# HLW8012-Demo.net
KiCad netlist of a schematic drawn in Altium Designer
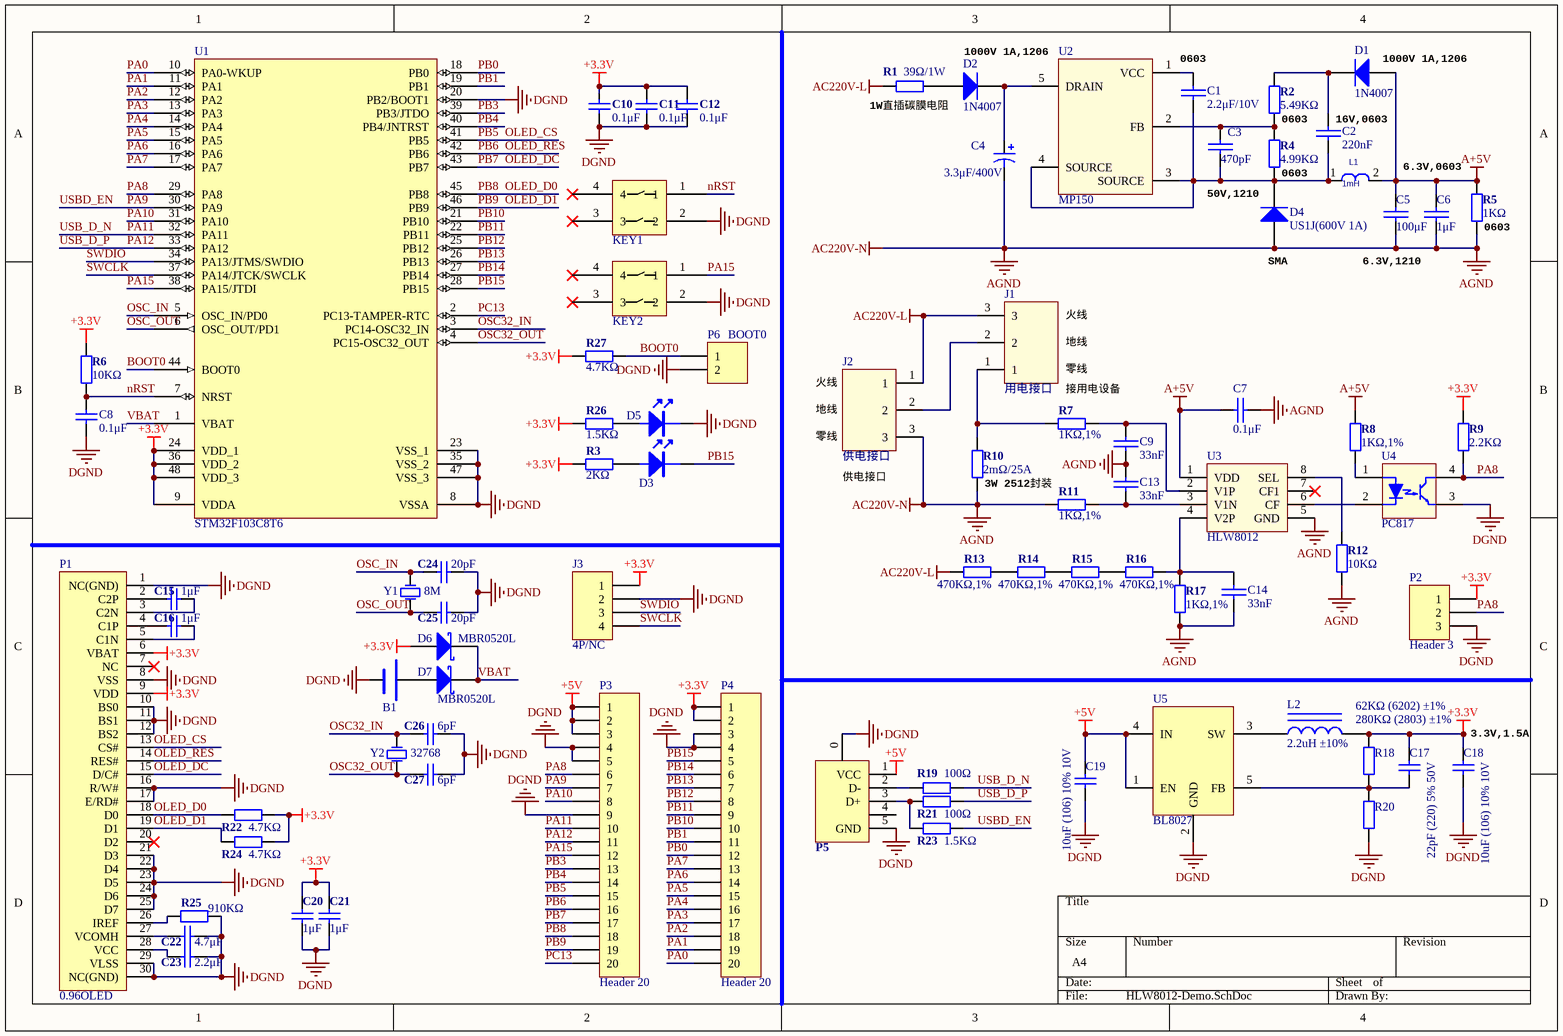
[diagram p0: HLW8012-Demo.SchDoc]

(export (version "E")
  (design (tool "Eeschema 10.0.6"))
  (components
    (comp (ref "B1")
      (value "BAT")
      (footprint "BATTERY SOCKET")
      (description "电池")
      (libsource (lib "OLED-0.96-Demo-MCU+Board") (part "BAT"))
    )
    (comp (ref "C1")
      (value "2.2μF/10V")
      (footprint "LC-0603_C")
      (description "贴片电容")
      (libsource (lib "原理图库") (part "CAP"))
    )
    (comp (ref "C2")
      (value "220nF")
      (footprint "LC-0603_C")
      (description "贴片电容")
      (libsource (lib "原理图库") (part "CAP"))
    )
    (comp (ref "C3")
      (value "470pF")
      (footprint "LC-0603_C")
      (description "贴片电容")
      (libsource (lib "原理图库") (part "CAP"))
    )
    (comp (ref "C4")
      (value "3.3μF/400V")
      (footprint "CAP-ELECT-TH-6.3X7")
      (description "直插电解电容")
      (fields (field (name "PUBLISHER") "Altium Limited"))
      (libsource (lib "Miscellaneous Devices") (part "Cap Pol1"))
    )
    (comp (ref "C5")
      (value "100μF")
      (footprint "LC-1210_C")
      (description "贴片电容")
      (libsource (lib "原理图库") (part "CAP"))
    )
    (comp (ref "C6")
      (value "1μF")
      (footprint "LC-0603_C")
      (description "贴片电容")
      (libsource (lib "原理图库") (part "CAP"))
    )
    (comp (ref "C7")
      (value "0.1μF")
      (footprint "LC-0603_C")
      (description "贴片电容")
      (libsource (lib "原理图库") (part "CAP"))
    )
    (comp (ref "C8")
      (value "0.1μF")
      (footprint "LC-0603_C")
      (description "贴片电容")
      (libsource (lib "FourAxis") (part "Cap"))
    )
    (comp (ref "C9")
      (value "33nF")
      (footprint "LC-0805_C")
      (description "贴片电容")
      (libsource (lib "原理图库") (part "CAP"))
    )
    (comp (ref "C10")
      (value "0.1μF")
      (footprint "LC-0603_C")
      (description "贴片电容")
      (libsource (lib "FourAxis") (part "Cap"))
    )
    (comp (ref "C11")
      (value "0.1μF")
      (footprint "LC-0603_C")
      (description "贴片电容")
      (libsource (lib "FourAxis") (part "Cap"))
    )
    (comp (ref "C12")
      (value "0.1μF")
      (footprint "LC-0603_C")
      (description "贴片电容")
      (libsource (lib "FourAxis") (part "Cap"))
    )
    (comp (ref "C13")
      (value "33nF")
      (footprint "LC-0805_C")
      (description "贴片电容")
      (libsource (lib "原理图库") (part "CAP"))
    )
    (comp (ref "C14")
      (value "33nF")
      (footprint "LC-0805_C")
      (description "贴片电容")
      (libsource (lib "原理图库") (part "CAP"))
    )
    (comp (ref "C15")
      (value "1μF")
      (footprint "LC-0603_C")
      (description "贴片电容")
      (libsource (lib "FourAxis") (part "Cap"))
    )
    (comp (ref "C16")
      (value "1μF")
      (footprint "LC-0603_C")
      (description "贴片电容")
      (libsource (lib "FourAxis") (part "Cap"))
    )
    (comp (ref "C17")
      (value "22pF (220) 5% 50V")
      (footprint "LC-0603_C")
      (description "贴片电容")
      (libsource (lib "Miscellaneous Devices LC") (part "0402 22pF (220) 5% 50V"))
    )
    (comp (ref "C18")
      (value "10uF (106) 10% 10V")
      (footprint "LC-0603_C")
      (description "贴片电容")
      (libsource (lib "Miscellaneous Devices LC") (part "0603 10uF (106) 10% 10V"))
    )
    (comp (ref "C19")
      (value "10uF (106) 10% 10V")
      (footprint "LC-0603_C")
      (description "贴片电容")
      (libsource (lib "Miscellaneous Devices LC") (part "0603 10uF (106) 10% 10V"))
    )
    (comp (ref "C20")
      (value "1μF")
      (footprint "LC-0603_C")
      (description "贴片电容")
      (libsource (lib "FourAxis") (part "Cap"))
    )
    (comp (ref "C21")
      (value "1μF")
      (footprint "LC-0603_C")
      (description "贴片电容")
      (libsource (lib "FourAxis") (part "Cap"))
    )
    (comp (ref "C22")
      (value "4.7μF")
      (footprint "LC-0603_C")
      (description "贴片电容")
      (libsource (lib "FourAxis") (part "Cap"))
    )
    (comp (ref "C23")
      (value "2.2μF")
      (footprint "LC-0603_C")
      (description "贴片电容")
      (libsource (lib "FourAxis") (part "Cap"))
    )
    (comp (ref "C24")
      (value "20pF")
      (footprint "LC-0603_C")
      (description "贴片电容")
      (libsource (lib "FourAxis") (part "Cap"))
    )
    (comp (ref "C25")
      (value "20pF")
      (footprint "LC-0603_C")
      (description "贴片电容")
      (libsource (lib "FourAxis") (part "Cap"))
    )
    (comp (ref "C26")
      (value "6pF")
      (footprint "LC-0603_C")
      (description "贴片电容")
      (libsource (lib "FourAxis") (part "Cap"))
    )
    (comp (ref "C27")
      (value "6pF")
      (footprint "LC-0603_C")
      (description "贴片电容")
      (libsource (lib "FourAxis") (part "Cap"))
    )
    (comp (ref "D1")
      (value "1N4007")
      (footprint "LC-SMA(DO-214AC)_S1")
      (description "贴片二极管")
      (fields (field (name "PUBLISHER") "Altium Limited"))
      (libsource (lib "Miscellaneous Devices") (part "Diode 1N5408"))
    )
    (comp (ref "D2")
      (value "1N4007")
      (footprint "LC-SMA(DO-214AC)_S1")
      (description "贴片二极管")
      (fields (field (name "PUBLISHER") "Altium Limited"))
      (libsource (lib "Miscellaneous Devices") (part "Diode 1N5408"))
    )
    (comp (ref "D3")
      (value "POWER")
      (footprint "LC-0603_LED_S1")
      (description "发光二极管")
      (libsource (lib "原理图库") (part "LED1"))
    )
    (comp (ref "D4")
      (value "US1J(600V 1A)")
      (footprint "LC-SMA(DO-214AC)_S1")
      (description "贴片二极管")
      (fields (field (name "PUBLISHER") "Altium Limited"))
      (libsource (lib "Miscellaneous Devices") (part "Diode 1N5408"))
    )
    (comp (ref "D5")
      (value "POWER")
      (footprint "LC-0603_LED_S1")
      (description "发光二极管")
      (libsource (lib "OLED-0.96-Demo-MCU+Board") (part "LED1"))
    )
    (comp (ref "D6")
      (value "MBR0520L")
      (footprint "LC-SOD-123")
      (description "贴片肖特基二极管")
      (fields (field (name "PUBLISHER") "Altium Limited"))
      (libsource (lib "USB-UART-RJ45") (part "Diode 18TQ045"))
    )
    (comp (ref "D7")
      (value "MBR0520L")
      (footprint "LC-SOD-123")
      (description "贴片肖特基二极管")
      (fields (field (name "PUBLISHER") "Altium Limited"))
      (libsource (lib "USB-UART-RJ45") (part "Diode 18TQ045"))
    )
    (comp (ref "J1")
      (value "用电接口")
      (footprint "3.81-3P")
      (description "直插接线端子")
      (libsource (lib "") (part "Port-3P_1"))
    )
    (comp (ref "J2")
      (value "供电接口")
      (footprint "3.81-3P")
      (description "直插接线端子")
      (libsource (lib "HLW8012-Demo") (part "Port-3P"))
    )
    (comp (ref "J3")
      (value "4P/NC")
      (footprint "HDR1X4")
      (description "接口")
      (fields (field (name "PUBLISHER") "Altium Limited"))
      (libsource (lib "Miscellaneous Connectors") (part "Header 4"))
    )
    (comp (ref "KEY1")
      (value "KEY")
      (footprint "KEY_4X4 - 6*6")
      (description "贴片轻触开关")
      (libsource (lib "STM32") (part "KEY"))
    )
    (comp (ref "KEY2")
      (value "KEY")
      (footprint "KEY_4X4 - 6*6")
      (description "贴片轻触开关")
      (libsource (lib "STM32") (part "KEY"))
    )
    (comp (ref "L1") (value "1mH") (description "直插绕线电感") (libsource (lib "*") (part "IND_8")))
    (comp (ref "L2")
      (value "2.2uH ±10%")
      (footprint "LC-0805_L")
      (description "贴片电感")
      (libsource (lib "Miscellaneous Devices LC") (part "0805 2.2uH 10%"))
    )
    (comp (ref "P1")
      (value "0.96OLED")
      (footprint "OLED_0.96")
      (description "接口")
      (fields (field (name "PUBLISHER") "Altium Limited"))
      (libsource (lib "HLW8012-Demo") (part "0.96OLED"))
    )
    (comp (ref "P2")
      (value "Header 3")
      (footprint "HDR1X3")
      (description "Header, 3-Pin")
      (fields (field (name "PUBLISHER") "Altium Limited"))
      (libsource (lib "Miscellaneous Connectors") (part "Header 3"))
    )
    (comp (ref "P3")
      (value "Header 20")
      (footprint "HDR1X20")
      (description "Header, 20-Pin")
      (fields (field (name "PUBLISHER") "Altium Limited"))
      (libsource (lib "Miscellaneous Connectors") (part "Header 20"))
    )
    (comp (ref "P4")
      (value "Header 20")
      (footprint "HDR1X20")
      (description "Header, 20-Pin")
      (fields (field (name "PUBLISHER") "Altium Limited"))
      (libsource (lib "Miscellaneous Connectors") (part "Header 20"))
    )
    (comp (ref "P5")
      (value "Micro USB,母头")
      (footprint "MicroUSB2")
      (description "接口")
      (libsource (lib "SU-IOT_v2.0") (part "microUSB"))
    )
    (comp (ref "P6")
      (value "BOOT0")
      (footprint "HDR1X2")
      (description "Header, 2-Pin")
      (fields (field (name "PUBLISHER") "Altium Limited"))
      (libsource (lib "Miscellaneous Connectors") (part "Header 2"))
    )
    (comp (ref "R1")
      (value "39Ω/1W")
      (footprint "R-1W-THT")
      (description "贴片电阻")
      (libsource (lib "") (part "电阻_1"))
    )
    (comp (ref "R2")
      (value "5.49KΩ")
      (footprint "LC-0603_R")
      (description "贴片电阻")
      (libsource (lib "") (part "电阻_3"))
    )
    (comp (ref "R3")
      (value "2KΩ")
      (footprint "LC-0603_R")
      (description "贴片电阻")
      (libsource (lib "FourAxis") (part "电阻"))
    )
    (comp (ref "R4")
      (value "4.99KΩ")
      (footprint "LC-0603_R")
      (description "贴片电阻")
      (libsource (lib "") (part "电阻_3"))
    )
    (comp (ref "R5")
      (value "1KΩ")
      (footprint "LC-0805_R")
      (description "贴片电阻")
      (libsource (lib "") (part "电阻_3"))
    )
    (comp (ref "R6")
      (value "10KΩ")
      (footprint "LC-0603_R")
      (description "贴片电阻")
      (libsource (lib "") (part "电阻_3"))
    )
    (comp (ref "R7")
      (value "1KΩ,1%")
      (footprint "LC-0805_R")
      (description "贴片电阻")
      (libsource (lib "FourAxis") (part "电阻"))
    )
    (comp (ref "R8")
      (value "1KΩ,1%")
      (footprint "LC-0805_R")
      (description "贴片电阻")
      (libsource (lib "") (part "电阻_3"))
    )
    (comp (ref "R9")
      (value "2.2KΩ")
      (footprint "LC-0603_R")
      (description "贴片电阻")
      (libsource (lib "") (part "电阻_3"))
    )
    (comp (ref "R10")
      (value "2mΩ/25A")
      (footprint "R2512")
      (description "贴片电阻")
      (libsource (lib "") (part "电阻_2"))
    )
    (comp (ref "R11")
      (value "1KΩ,1%")
      (footprint "LC-0805_R")
      (description "贴片电阻")
      (libsource (lib "FourAxis") (part "电阻"))
    )
    (comp (ref "R12")
      (value "10KΩ")
      (footprint "LC-0603_R")
      (description "贴片电阻")
      (libsource (lib "") (part "电阻_2"))
    )
    (comp (ref "R13")
      (value "470KΩ,1%")
      (footprint "LC-0805_R")
      (description "贴片电阻")
      (libsource (lib "FourAxis") (part "电阻"))
    )
    (comp (ref "R14")
      (value "470KΩ,1%")
      (footprint "LC-0805_R")
      (description "贴片电阻")
      (libsource (lib "FourAxis") (part "电阻"))
    )
    (comp (ref "R15")
      (value "470KΩ,1%")
      (footprint "LC-0805_R")
      (description "贴片电阻")
      (libsource (lib "FourAxis") (part "电阻"))
    )
    (comp (ref "R16")
      (value "470KΩ,1%")
      (footprint "LC-0805_R")
      (description "贴片电阻")
      (libsource (lib "FourAxis") (part "电阻"))
    )
    (comp (ref "R17")
      (value "1KΩ,1%")
      (footprint "LC-0805_R")
      (description "贴片电阻")
      (libsource (lib "") (part "电阻_2"))
    )
    (comp (ref "R18")
      (value "280KΩ (2803) ±1%")
      (footprint "LC-0603_R")
      (description "贴片电阻")
      (libsource (lib "") (part "0805 62KΩ (6202) 1%_1"))
    )
    (comp (ref "R19")
      (value "100Ω")
      (footprint "LC-0603_R")
      (description "贴片电阻")
      (libsource (lib "FourAxis") (part "电阻"))
    )
    (comp (ref "R20")
      (value "62KΩ (6202) ±1%")
      (footprint "LC-0603_R")
      (description "贴片电阻")
      (libsource (lib "Miscellaneous Devices LC") (part "0805 62KΩ (6202) 1%"))
    )
    (comp (ref "R21")
      (value "100Ω")
      (footprint "LC-0603_R")
      (description "贴片电阻")
      (libsource (lib "FourAxis") (part "电阻"))
    )
    (comp (ref "R22")
      (value "4.7KΩ")
      (footprint "LC-0603_R")
      (description "贴片电阻")
      (libsource (lib "FourAxis") (part "电阻"))
    )
    (comp (ref "R23")
      (value "1.5KΩ")
      (footprint "LC-0603_R")
      (description "贴片电阻")
      (libsource (lib "FourAxis") (part "电阻"))
    )
    (comp (ref "R24")
      (value "4.7KΩ")
      (footprint "LC-0603_R")
      (description "贴片电阻")
      (libsource (lib "FourAxis") (part "电阻"))
    )
    (comp (ref "R25")
      (value "910KΩ")
      (footprint "LC-0603_R")
      (description "贴片电阻")
      (libsource (lib "") (part "电阻_2"))
    )
    (comp (ref "R26")
      (value "1.5KΩ")
      (footprint "LC-0603_R")
      (description "贴片电阻")
      (libsource (lib "FourAxis") (part "电阻"))
    )
    (comp (ref "R27")
      (value "4.7KΩ")
      (footprint "LC-0603_R")
      (description "贴片电阻")
      (libsource (lib "FourAxis") (part "电阻"))
    )
    (comp (ref "U1")
      (value "STM32F103C8T6")
      (footprint "LC-LQFP-48_7x7x05P")
      (description "IC")
      (fields (field (name "PUBLISHER") "Altium Limited"))
      (libsource (lib "FourAxis") (part "STM32F103CBT6"))
    )
    (comp (ref "U2")
      (value "MP150")
      (footprint "LC-SOT-23-5")
      (description "IC")
      (libsource (lib "HLW8012-Demo") (part "MP150"))
    )
    (comp (ref "U3")
      (value "HLW8012")
      (footprint "LC-SOP-8_150mil")
      (description "IC")
      (libsource (lib "HLW8012-Demo") (part "HLW8012"))
    )
    (comp (ref "U4")
      (value "PC817")
      (footprint "LC-SMD-4")
      (description "IC")
      (libsource (lib "HLW8012-Demo") (part "PS2501L-1-F3-A"))
    )
    (comp (ref "U5")
      (value "BL8027")
      (footprint "LC-SOT-23-5")
      (description "IC")
      (libsource (lib "OLED-0.96-Demo-MCU+Board") (part "DC-DC"))
    )
    (comp (ref "Y1")
      (value "8M")
      (footprint "LC-HC-49SMD")
      (description "晶振（直插）")
      (fields (field (name "PUBLISHER") "Altium Limited"))
      (libsource (lib "") (part "XTAL_1_1"))
    )
    (comp (ref "Y2")
      (value "32768")
      (footprint "MC-306")
      (description "晶振（直插）")
      (fields (field (name "PUBLISHER") "Altium Limited"))
      (libsource (lib "OLED-0.96-Demo-MCU+Board") (part "XTAL_1"))
    )
  )
  (nets
    (net (code "1") (name "+3.3V") (class "Default")
      (node (ref "C10") (pin "2") (pinfunction "2_2") (pintype "passive"))
      (node (ref "C11") (pin "2") (pinfunction "2_2") (pintype "passive"))
      (node (ref "C12") (pin "2") (pinfunction "2_2") (pintype "passive"))
      (node (ref "C17") (pin "2") (pinfunction "2_2") (pintype "passive"))
      (node (ref "C18") (pin "2") (pinfunction "2_2") (pintype "passive"))
      (node (ref "C20") (pin "2") (pinfunction "2_2") (pintype "passive"))
      (node (ref "C21") (pin "2") (pinfunction "2_2") (pintype "passive"))
      (node (ref "D6") (pin "1") (pinfunction "A_1") (pintype "passive"))
      (node (ref "J3") (pin "1") (pinfunction "1_1") (pintype "passive"))
      (node (ref "L2") (pin "2") (pinfunction "2_2") (pintype "passive"))
      (node (ref "P1") (pin "6") (pinfunction "VBAT_6") (pintype "passive"))
      (node (ref "P1") (pin "9") (pinfunction "VDD_9") (pintype "passive"))
      (node (ref "P2") (pin "1") (pinfunction "1_1") (pintype "passive"))
      (node (ref "P4") (pin "1") (pinfunction "1_1") (pintype "passive"))
      (node (ref "P4") (pin "2") (pinfunction "2_2") (pintype "passive"))
      (node (ref "R18") (pin "1") (pinfunction "1_1") (pintype "passive"))
      (node (ref "R22") (pin "1") (pinfunction "1_1") (pintype "passive"))
      (node (ref "R24") (pin "1") (pinfunction "1_1") (pintype "passive"))
      (node (ref "R26") (pin "2") (pinfunction "2_2") (pintype "passive"))
      (node (ref "R27") (pin "2") (pinfunction "2_2") (pintype "passive"))
      (node (ref "R3") (pin "2") (pinfunction "2_2") (pintype "passive"))
      (node (ref "R6") (pin "2") (pinfunction "2_2") (pintype "passive"))
      (node (ref "R9") (pin "2") (pinfunction "2_2") (pintype "passive"))
      (node (ref "U1") (pin "24") (pinfunction "VDD_1_24") (pintype "power_in"))
      (node (ref "U1") (pin "36") (pinfunction "VDD_2_36") (pintype "power_in"))
      (node (ref "U1") (pin "48") (pinfunction "VDD_3_48") (pintype "power_in"))
      (node (ref "U1") (pin "9") (pinfunction "VDDA_9") (pintype "power_in"))
    )
    (net (code "2") (name "+5V") (class "Default")
      (node (ref "C19") (pin "2") (pinfunction "2_2") (pintype "passive"))
      (node (ref "P3") (pin "1") (pinfunction "1_1") (pintype "passive"))
      (node (ref "P3") (pin "2") (pinfunction "2_2") (pintype "passive"))
      (node (ref "P3") (pin "3") (pinfunction "3_3") (pintype "passive"))
      (node (ref "P5") (pin "1") (pinfunction "VCC_1") (pintype "passive"))
      (node (ref "U5") (pin "1") (pinfunction "EN_1") (pintype "passive"))
      (node (ref "U5") (pin "4") (pinfunction "IN_4") (pintype "passive"))
    )
    (net (code "3") (name "/BOOT0") (class "Default")
      (node (ref "P6") (pin "1") (pinfunction "1_1") (pintype "passive"))
      (node (ref "R27") (pin "1") (pinfunction "1_1") (pintype "passive"))
      (node (ref "U1") (pin "44") (pinfunction "BOOT0_44") (pintype "input"))
    )
    (net (code "4") (name "/OLED_CS") (class "Default")
      (node (ref "P1") (pin "13") (pinfunction "CS#_13") (pintype "passive"))
      (node (ref "P3") (pin "15") (pinfunction "15_15") (pintype "passive"))
      (node (ref "U1") (pin "41") (pinfunction "PB5_41") (pintype "bidirectional"))
    )
    (net (code "5") (name "/OLED_D0") (class "Default")
      (node (ref "P1") (pin "18") (pinfunction "D0_18") (pintype "passive"))
      (node (ref "P3") (pin "18") (pinfunction "18_18") (pintype "passive"))
      (node (ref "R22") (pin "2") (pinfunction "2_2") (pintype "passive"))
      (node (ref "U1") (pin "45") (pinfunction "PB8_45") (pintype "bidirectional"))
    )
    (net (code "6") (name "/OLED_D1") (class "Default")
      (node (ref "P1") (pin "19") (pinfunction "D1_19") (pintype "passive"))
      (node (ref "P3") (pin "19") (pinfunction "19_19") (pintype "passive"))
      (node (ref "R24") (pin "2") (pinfunction "2_2") (pintype "passive"))
      (node (ref "U1") (pin "46") (pinfunction "PB9_46") (pintype "bidirectional"))
    )
    (net (code "7") (name "/OLED_DC") (class "Default")
      (node (ref "P1") (pin "15") (pinfunction "D/C#_15") (pintype "passive"))
      (node (ref "P3") (pin "17") (pinfunction "17_17") (pintype "passive"))
      (node (ref "U1") (pin "43") (pinfunction "PB7_43") (pintype "bidirectional"))
    )
    (net (code "8") (name "/OLED_RES") (class "Default")
      (node (ref "P1") (pin "14") (pinfunction "RES#_14") (pintype "passive"))
      (node (ref "P3") (pin "16") (pinfunction "16_16") (pintype "passive"))
      (node (ref "U1") (pin "42") (pinfunction "PB6_42") (pintype "bidirectional"))
    )
    (net (code "9") (name "/OSC32_IN") (class "Default")
      (node (ref "C26") (pin "1") (pinfunction "1_1") (pintype "passive"))
      (node (ref "U1") (pin "3") (pinfunction "PC14-OSC32_IN_3") (pintype "bidirectional"))
      (node (ref "Y2") (pin "1") (pinfunction "1_1") (pintype "passive"))
    )
    (net (code "10") (name "/OSC32_OUT") (class "Default")
      (node (ref "C27") (pin "1") (pinfunction "1_1") (pintype "passive"))
      (node (ref "U1") (pin "4") (pinfunction "PC15-OSC32_OUT_4") (pintype "bidirectional"))
      (node (ref "Y2") (pin "4") (pinfunction "4_4") (pintype "passive"))
    )
    (net (code "11") (name "/OSC_IN") (class "Default")
      (node (ref "C24") (pin "1") (pinfunction "1_1") (pintype "passive"))
      (node (ref "U1") (pin "5") (pinfunction "OSC_IN/PD0_5") (pintype "input"))
      (node (ref "Y1") (pin "1") (pinfunction "1_1") (pintype "passive"))
    )
    (net (code "12") (name "/OSC_OUT") (class "Default")
      (node (ref "C25") (pin "1") (pinfunction "1_1") (pintype "passive"))
      (node (ref "U1") (pin "6") (pinfunction "OSC_OUT/PD1_6") (pintype "output"))
      (node (ref "Y1") (pin "2") (pinfunction "2_2") (pintype "passive"))
    )
    (net (code "13") (name "/PA0") (class "Default")
      (node (ref "P4") (pin "20") (pinfunction "20_20") (pintype "passive"))
      (node (ref "U1") (pin "10") (pinfunction "PA0-WKUP_10") (pintype "bidirectional"))
    )
    (net (code "14") (name "/PA1") (class "Default")
      (node (ref "P4") (pin "19") (pinfunction "19_19") (pintype "passive"))
      (node (ref "U1") (pin "11") (pinfunction "PA1_11") (pintype "bidirectional"))
    )
    (net (code "15") (name "/PA2") (class "Default")
      (node (ref "P4") (pin "18") (pinfunction "18_18") (pintype "passive"))
      (node (ref "U1") (pin "12") (pinfunction "PA2_12") (pintype "bidirectional"))
    )
    (net (code "16") (name "/PA3") (class "Default")
      (node (ref "P4") (pin "17") (pinfunction "17_17") (pintype "passive"))
      (node (ref "U1") (pin "13") (pinfunction "PA3_13") (pintype "bidirectional"))
    )
    (net (code "17") (name "/PA4") (class "Default")
      (node (ref "P4") (pin "16") (pinfunction "16_16") (pintype "passive"))
      (node (ref "U1") (pin "14") (pinfunction "PA4_14") (pintype "bidirectional"))
    )
    (net (code "18") (name "/PA5") (class "Default")
      (node (ref "P4") (pin "15") (pinfunction "15_15") (pintype "passive"))
      (node (ref "U1") (pin "15") (pinfunction "PA5_15") (pintype "bidirectional"))
    )
    (net (code "19") (name "/PA6") (class "Default")
      (node (ref "P4") (pin "14") (pinfunction "14_14") (pintype "passive"))
      (node (ref "U1") (pin "16") (pinfunction "PA6_16") (pintype "bidirectional"))
    )
    (net (code "20") (name "/PA7") (class "Default")
      (node (ref "P4") (pin "13") (pinfunction "13_13") (pintype "passive"))
      (node (ref "U1") (pin "17") (pinfunction "PA7_17") (pintype "bidirectional"))
    )
    (net (code "21") (name "/PA8") (class "Default")
      (node (ref "P2") (pin "2") (pinfunction "2_2") (pintype "passive"))
      (node (ref "P3") (pin "6") (pinfunction "6_6") (pintype "passive"))
      (node (ref "R9") (pin "1") (pinfunction "1_1") (pintype "passive"))
      (node (ref "U1") (pin "29") (pinfunction "PA8_29") (pintype "bidirectional"))
      (node (ref "U4") (pin "4") (pinfunction "K2_4") (pintype "passive"))
    )
    (net (code "22") (name "/PA9") (class "Default")
      (node (ref "P3") (pin "7") (pinfunction "7_7") (pintype "passive"))
      (node (ref "R23") (pin "1") (pinfunction "1_1") (pintype "passive"))
      (node (ref "U1") (pin "30") (pinfunction "PA9_30") (pintype "bidirectional"))
    )
    (net (code "23") (name "/PA10") (class "Default")
      (node (ref "P3") (pin "8") (pinfunction "8_8") (pintype "passive"))
      (node (ref "U1") (pin "31") (pinfunction "PA10_31") (pintype "bidirectional"))
    )
    (net (code "24") (name "/PA11") (class "Default")
      (node (ref "P3") (pin "10") (pinfunction "10_10") (pintype "passive"))
      (node (ref "R19") (pin "1") (pinfunction "1_1") (pintype "passive"))
      (node (ref "U1") (pin "32") (pinfunction "PA11_32") (pintype "bidirectional"))
    )
    (net (code "25") (name "/PA12") (class "Default")
      (node (ref "P3") (pin "11") (pinfunction "11_11") (pintype "passive"))
      (node (ref "R21") (pin "1") (pinfunction "1_1") (pintype "passive"))
      (node (ref "U1") (pin "33") (pinfunction "PA12_33") (pintype "bidirectional"))
    )
    (net (code "26") (name "/PA15") (class "Default")
      (node (ref "KEY2") (pin "1") (pinfunction "1_1") (pintype "passive"))
      (node (ref "P3") (pin "12") (pinfunction "12_12") (pintype "passive"))
      (node (ref "U1") (pin "38") (pinfunction "PA15/JTDI_38") (pintype "bidirectional"))
    )
    (net (code "27") (name "/PB0") (class "Default")
      (node (ref "P4") (pin "12") (pinfunction "12_12") (pintype "passive"))
      (node (ref "U1") (pin "18") (pinfunction "PB0_18") (pintype "bidirectional"))
    )
    (net (code "28") (name "/PB1") (class "Default")
      (node (ref "P4") (pin "11") (pinfunction "11_11") (pintype "passive"))
      (node (ref "U1") (pin "19") (pinfunction "PB1_19") (pintype "bidirectional"))
    )
    (net (code "29") (name "/PB3") (class "Default")
      (node (ref "P3") (pin "13") (pinfunction "13_13") (pintype "passive"))
      (node (ref "U1") (pin "39") (pinfunction "PB3/JTDO_39") (pintype "bidirectional"))
    )
    (net (code "30") (name "/PB4") (class "Default")
      (node (ref "P3") (pin "14") (pinfunction "14_14") (pintype "passive"))
      (node (ref "U1") (pin "40") (pinfunction "PB4/JNTRST_40") (pintype "bidirectional"))
    )
    (net (code "31") (name "/PB10") (class "Default")
      (node (ref "P4") (pin "10") (pinfunction "10_10") (pintype "passive"))
      (node (ref "U1") (pin "21") (pinfunction "PB10_21") (pintype "bidirectional"))
    )
    (net (code "32") (name "/PB11") (class "Default")
      (node (ref "P4") (pin "9") (pinfunction "9_9") (pintype "passive"))
      (node (ref "U1") (pin "22") (pinfunction "PB11_22") (pintype "bidirectional"))
    )
    (net (code "33") (name "/PB12") (class "Default")
      (node (ref "P4") (pin "8") (pinfunction "8_8") (pintype "passive"))
      (node (ref "U1") (pin "25") (pinfunction "PB12_25") (pintype "bidirectional"))
    )
    (net (code "34") (name "/PB13") (class "Default")
      (node (ref "P4") (pin "7") (pinfunction "7_7") (pintype "passive"))
      (node (ref "U1") (pin "26") (pinfunction "PB13_26") (pintype "bidirectional"))
    )
    (net (code "35") (name "/PB14") (class "Default")
      (node (ref "P4") (pin "6") (pinfunction "6_6") (pintype "passive"))
      (node (ref "U1") (pin "27") (pinfunction "PB14_27") (pintype "bidirectional"))
    )
    (net (code "36") (name "/PB15") (class "Default")
      (node (ref "D3") (pin "K") (pinfunction "K_K") (pintype "passive"))
      (node (ref "P4") (pin "5") (pinfunction "5_5") (pintype "passive"))
      (node (ref "U1") (pin "28") (pinfunction "PB15_28") (pintype "bidirectional"))
    )
    (net (code "37") (name "/PC13") (class "Default")
      (node (ref "P3") (pin "20") (pinfunction "20_20") (pintype "passive"))
      (node (ref "U1") (pin "2") (pinfunction "PC13-TAMPER-RTC_2") (pintype "bidirectional"))
    )
    (net (code "38") (name "/SWCLK") (class "Default")
      (node (ref "J3") (pin "4") (pinfunction "4_4") (pintype "passive"))
      (node (ref "U1") (pin "37") (pinfunction "PA14/JTCK/SWCLK_37") (pintype "bidirectional"))
    )
    (net (code "39") (name "/SWDIO") (class "Default")
      (node (ref "J3") (pin "3") (pinfunction "3_3") (pintype "passive"))
      (node (ref "U1") (pin "34") (pinfunction "PA13/JTMS/SWDIO_34") (pintype "bidirectional"))
    )
    (net (code "40") (name "/VBAT") (class "Default")
      (node (ref "D6") (pin "2") (pinfunction "K_2") (pintype "passive"))
      (node (ref "D7") (pin "2") (pinfunction "K_2") (pintype "passive"))
      (node (ref "U1") (pin "1") (pinfunction "VBAT_1") (pintype "power_in"))
    )
    (net (code "41") (name "/nRST") (class "Default")
      (node (ref "C8") (pin "2") (pinfunction "2_2") (pintype "passive"))
      (node (ref "KEY1") (pin "1") (pinfunction "1_1") (pintype "passive"))
      (node (ref "R6") (pin "1") (pinfunction "1_1") (pintype "passive"))
      (node (ref "U1") (pin "7") (pinfunction "NRST_7") (pintype "bidirectional"))
    )
    (net (code "42") (name "A+5V") (class "Default")
      (node (ref "C5") (pin "2") (pinfunction "2_2") (pintype "passive"))
      (node (ref "C6") (pin "2") (pinfunction "2_2") (pintype "passive"))
      (node (ref "C7") (pin "1") (pinfunction "1_1") (pintype "passive"))
      (node (ref "D1") (pin "1") (pinfunction "A_1") (pintype "passive"))
      (node (ref "L1") (pin "2") (pinfunction "2_2") (pintype "passive"))
      (node (ref "R5") (pin "2") (pinfunction "2_2") (pintype "passive"))
      (node (ref "R8") (pin "2") (pinfunction "2_2") (pintype "passive"))
      (node (ref "U3") (pin "1") (pinfunction "VDD_1") (pintype "passive"))
    )
    (net (code "43") (name "AC220V-L") (class "Default")
      (node (ref "J1") (pin "3") (pinfunction "3_3") (pintype "passive"))
      (node (ref "J2") (pin "1") (pinfunction "1_1") (pintype "passive"))
      (node (ref "R1") (pin "1") (pinfunction "1_1") (pintype "passive"))
      (node (ref "R13") (pin "2") (pinfunction "2_2") (pintype "passive"))
    )
    (net (code "44") (name "AC220V-N") (class "Default")
      (node (ref "C13") (pin "1") (pinfunction "1_1") (pintype "passive"))
      (node (ref "C14") (pin "2") (pinfunction "2_2") (pintype "passive"))
      (node (ref "C4") (pin "2") (pinfunction "2_2") (pintype "passive"))
      (node (ref "C5") (pin "1") (pinfunction "1_1") (pintype "passive"))
      (node (ref "C6") (pin "1") (pinfunction "1_1") (pintype "passive"))
      (node (ref "C7") (pin "2") (pinfunction "2_2") (pintype "passive"))
      (node (ref "C9") (pin "2") (pinfunction "2_2") (pintype "passive"))
      (node (ref "D4") (pin "1") (pinfunction "A_1") (pintype "passive"))
      (node (ref "J2") (pin "3") (pinfunction "3_3") (pintype "passive"))
      (node (ref "R10") (pin "2") (pinfunction "2_2") (pintype "passive"))
      (node (ref "R11") (pin "2") (pinfunction "2_2") (pintype "passive"))
      (node (ref "R12") (pin "2") (pinfunction "2_2") (pintype "passive"))
      (node (ref "R17") (pin "2") (pinfunction "2_2") (pintype "passive"))
      (node (ref "R5") (pin "1") (pinfunction "1_1") (pintype "passive"))
      (node (ref "U3") (pin "5") (pinfunction "GND_5") (pintype "passive"))
    )
    (net (code "45") (name "DGND") (class "Default")
      (node (ref "B1") (pin "2") (pinfunction "2_2") (pintype "passive"))
      (node (ref "C10") (pin "1") (pinfunction "1_1") (pintype "passive"))
      (node (ref "C11") (pin "1") (pinfunction "1_1") (pintype "passive"))
      (node (ref "C12") (pin "1") (pinfunction "1_1") (pintype "passive"))
      (node (ref "C18") (pin "1") (pinfunction "1_1") (pintype "passive"))
      (node (ref "C19") (pin "1") (pinfunction "1_1") (pintype "passive"))
      (node (ref "C20") (pin "1") (pinfunction "1_1") (pintype "passive"))
      (node (ref "C21") (pin "1") (pinfunction "1_1") (pintype "passive"))
      (node (ref "C22") (pin "1") (pinfunction "1_1") (pintype "passive"))
      (node (ref "C23") (pin "1") (pinfunction "1_1") (pintype "passive"))
      (node (ref "C24") (pin "2") (pinfunction "2_2") (pintype "passive"))
      (node (ref "C25") (pin "2") (pinfunction "2_2") (pintype "passive"))
      (node (ref "C26") (pin "2") (pinfunction "2_2") (pintype "passive"))
      (node (ref "C27") (pin "2") (pinfunction "2_2") (pintype "passive"))
      (node (ref "C8") (pin "1") (pinfunction "1_1") (pintype "passive"))
      (node (ref "D5") (pin "K") (pinfunction "K_K") (pintype "passive"))
      (node (ref "J3") (pin "2") (pinfunction "2_2") (pintype "passive"))
      (node (ref "KEY1") (pin "2") (pinfunction "2_2") (pintype "passive"))
      (node (ref "KEY2") (pin "2") (pinfunction "2_2") (pintype "passive"))
      (node (ref "P1") (pin "1") (pinfunction "NC(GND)_1") (pintype "passive"))
      (node (ref "P1") (pin "10") (pinfunction "BS0_10") (pintype "passive"))
      (node (ref "P1") (pin "11") (pinfunction "BS1_11") (pintype "passive"))
      (node (ref "P1") (pin "12") (pinfunction "BS2_12") (pintype "passive"))
      (node (ref "P1") (pin "16") (pinfunction "R/W#_16") (pintype "passive"))
      (node (ref "P1") (pin "17") (pinfunction "E/RD#_17") (pintype "passive"))
      (node (ref "P1") (pin "21") (pinfunction "D3_21") (pintype "passive"))
      (node (ref "P1") (pin "22") (pinfunction "D4_22") (pintype "passive"))
      (node (ref "P1") (pin "23") (pinfunction "D5_23") (pintype "passive"))
      (node (ref "P1") (pin "24") (pinfunction "D6_24") (pintype "passive"))
      (node (ref "P1") (pin "25") (pinfunction "D7_25") (pintype "passive"))
      (node (ref "P1") (pin "29") (pinfunction "VLSS_29") (pintype "passive"))
      (node (ref "P1") (pin "30") (pinfunction "NC(GND)_30") (pintype "passive"))
      (node (ref "P1") (pin "8") (pinfunction "VSS_8") (pintype "passive"))
      (node (ref "P2") (pin "3") (pinfunction "3_3") (pintype "passive"))
      (node (ref "P3") (pin "4") (pinfunction "4_4") (pintype "passive"))
      (node (ref "P3") (pin "5") (pinfunction "5_5") (pintype "passive"))
      (node (ref "P3") (pin "9") (pinfunction "9_9") (pintype "passive"))
      (node (ref "P4") (pin "3") (pinfunction "3_3") (pintype "passive"))
      (node (ref "P4") (pin "4") (pinfunction "4_4") (pintype "passive"))
      (node (ref "P5") (pin "0") (pinfunction "GND_0") (pintype "passive"))
      (node (ref "P5") (pin "5") (pinfunction "GND_5") (pintype "passive"))
      (node (ref "P6") (pin "2") (pinfunction "2_2") (pintype "passive"))
      (node (ref "R20") (pin "1") (pinfunction "1_1") (pintype "passive"))
      (node (ref "R25") (pin "1") (pinfunction "1_1") (pintype "passive"))
      (node (ref "U1") (pin "20") (pinfunction "PB2/BOOT1_20") (pintype "bidirectional"))
      (node (ref "U1") (pin "23") (pinfunction "VSS_1_23") (pintype "power_in"))
      (node (ref "U1") (pin "35") (pinfunction "VSS_2_35") (pintype "power_in"))
      (node (ref "U1") (pin "47") (pinfunction "VSS_3_47") (pintype "power_in"))
      (node (ref "U1") (pin "8") (pinfunction "VSSA_8") (pintype "power_in"))
      (node (ref "U4") (pin "3") (pinfunction "A2_3") (pintype "passive"))
      (node (ref "U5") (pin "2") (pinfunction "GND_2") (pintype "passive"))
    )
    (net (code "46") (name "Net-(D1-K)") (class "Default")
      (node (ref "C2") (pin "2") (pinfunction "2_2") (pintype "passive"))
      (node (ref "D1") (pin "2") (pinfunction "K_2") (pintype "passive"))
      (node (ref "R2") (pin "2") (pinfunction "2_2") (pintype "passive"))
    )
    (net (code "47") (name "Net-(D2-A)") (class "Default")
      (node (ref "D2") (pin "1") (pinfunction "A_1") (pintype "passive"))
      (node (ref "R1") (pin "2") (pinfunction "2_2") (pintype "passive"))
    )
    (net (code "48") (name "Net-(D2-K)") (class "Default")
      (node (ref "C4") (pin "1") (pinfunction "1_1") (pintype "passive"))
      (node (ref "D2") (pin "2") (pinfunction "K_2") (pintype "passive"))
      (node (ref "U2") (pin "5") (pinfunction "DRAIN_5") (pintype "passive"))
    )
    (net (code "49") (name "Net-(D3-PadA)") (class "Default")
      (node (ref "D3") (pin "A") (pinfunction "A_A") (pintype "passive"))
      (node (ref "R3") (pin "1") (pinfunction "1_1") (pintype "passive"))
    )
    (net (code "50") (name "Net-(D4-K)") (class "Default")
      (node (ref "C1") (pin "1") (pinfunction "1_1") (pintype "passive"))
      (node (ref "C2") (pin "1") (pinfunction "1_1") (pintype "passive"))
      (node (ref "C3") (pin "1") (pinfunction "1_1") (pintype "passive"))
      (node (ref "D4") (pin "2") (pinfunction "K_2") (pintype "passive"))
      (node (ref "L1") (pin "1") (pinfunction "1_1") (pintype "passive"))
      (node (ref "R4") (pin "1") (pinfunction "1_1") (pintype "passive"))
      (node (ref "U2") (pin "3") (pinfunction "SOURCE_3") (pintype "passive"))
      (node (ref "U2") (pin "4") (pinfunction "SOURCE_4") (pintype "passive"))
    )
    (net (code "51") (name "Net-(D5-PadA)") (class "Default")
      (node (ref "D5") (pin "A") (pinfunction "A_A") (pintype "passive"))
      (node (ref "R26") (pin "1") (pinfunction "1_1") (pintype "passive"))
    )
    (net (code "52") (name "Net-(D7-A)") (class "Default")
      (node (ref "B1") (pin "1") (pinfunction "1_1") (pintype "passive"))
      (node (ref "D7") (pin "1") (pinfunction "A_1") (pintype "passive"))
    )
    (net (code "53") (name "Net-(J1-Pad1)") (class "Default")
      (node (ref "J1") (pin "1") (pinfunction "1_1") (pintype "passive"))
      (node (ref "R10") (pin "1") (pinfunction "1_1") (pintype "passive"))
      (node (ref "R7") (pin "2") (pinfunction "2_2") (pintype "passive"))
    )
    (net (code "54") (name "Net-(J1-Pad2)") (class "Default")
      (node (ref "J1") (pin "2") (pinfunction "2_2") (pintype "passive"))
      (node (ref "J2") (pin "2") (pinfunction "2_2") (pintype "passive"))
    )
    (net (code "55") (name "Net-(P1-C1N)") (class "Default")
      (node (ref "C16") (pin "1") (pinfunction "1_1") (pintype "passive"))
      (node (ref "P1") (pin "5") (pinfunction "C1N_5") (pintype "passive"))
    )
    (net (code "56") (name "Net-(P1-C1P)") (class "Default")
      (node (ref "C16") (pin "2") (pinfunction "2_2") (pintype "passive"))
      (node (ref "P1") (pin "4") (pinfunction "C1P_4") (pintype "passive"))
    )
    (net (code "57") (name "Net-(P1-C2N)") (class "Default")
      (node (ref "C15") (pin "1") (pinfunction "1_1") (pintype "passive"))
      (node (ref "P1") (pin "3") (pinfunction "C2N_3") (pintype "passive"))
    )
    (net (code "58") (name "Net-(P1-C2P)") (class "Default")
      (node (ref "C15") (pin "2") (pinfunction "2_2") (pintype "passive"))
      (node (ref "P1") (pin "2") (pinfunction "C2P_2") (pintype "passive"))
    )
    (net (code "59") (name "Net-(P1-IREF)") (class "Default")
      (node (ref "P1") (pin "26") (pinfunction "IREF_26") (pintype "passive"))
      (node (ref "R25") (pin "2") (pinfunction "2_2") (pintype "passive"))
    )
    (net (code "60") (name "Net-(P1-VCC)") (class "Default")
      (node (ref "C23") (pin "2") (pinfunction "2_2") (pintype "passive"))
      (node (ref "P1") (pin "28") (pinfunction "VCC_28") (pintype "passive"))
    )
    (net (code "61") (name "Net-(P1-VCOMH)") (class "Default")
      (node (ref "C22") (pin "2") (pinfunction "2_2") (pintype "passive"))
      (node (ref "P1") (pin "27") (pinfunction "VCOMH_27") (pintype "passive"))
    )
    (net (code "62") (name "Net-(P5-D+)") (class "Default")
      (node (ref "P5") (pin "3") (pinfunction "D+_3") (pintype "passive"))
      (node (ref "R21") (pin "2") (pinfunction "2_2") (pintype "passive"))
      (node (ref "R23") (pin "2") (pinfunction "2_2") (pintype "passive"))
    )
    (net (code "63") (name "Net-(P5-D-)") (class "Default")
      (node (ref "P5") (pin "2") (pinfunction "D-_2") (pintype "passive"))
      (node (ref "R19") (pin "2") (pinfunction "2_2") (pintype "passive"))
    )
    (net (code "64") (name "Net-(R13-Pad1)") (class "Default")
      (node (ref "R13") (pin "1") (pinfunction "1_1") (pintype "passive"))
      (node (ref "R14") (pin "2") (pinfunction "2_2") (pintype "passive"))
    )
    (net (code "65") (name "Net-(R14-Pad1)") (class "Default")
      (node (ref "R14") (pin "1") (pinfunction "1_1") (pintype "passive"))
      (node (ref "R15") (pin "2") (pinfunction "2_2") (pintype "passive"))
    )
    (net (code "66") (name "Net-(R15-Pad1)") (class "Default")
      (node (ref "R15") (pin "1") (pinfunction "1_1") (pintype "passive"))
      (node (ref "R16") (pin "2") (pinfunction "2_2") (pintype "passive"))
    )
    (net (code "67") (name "Net-(U2-FB)") (class "Default")
      (node (ref "C3") (pin "2") (pinfunction "2_2") (pintype "passive"))
      (node (ref "R2") (pin "1") (pinfunction "1_1") (pintype "passive"))
      (node (ref "R4") (pin "2") (pinfunction "2_2") (pintype "passive"))
      (node (ref "U2") (pin "2") (pinfunction "FB_2") (pintype "passive"))
    )
    (net (code "68") (name "Net-(U2-VCC)") (class "Default")
      (node (ref "C1") (pin "2") (pinfunction "2_2") (pintype "passive"))
      (node (ref "U2") (pin "1") (pinfunction "VCC_1") (pintype "passive"))
    )
    (net (code "69") (name "Net-(U3-CF)") (class "Default")
      (node (ref "U3") (pin "6") (pinfunction "CF_6") (pintype "passive"))
      (node (ref "U4") (pin "2") (pinfunction "K1_2") (pintype "passive"))
    )
    (net (code "70") (name "Net-(U3-SEL)") (class "Default")
      (node (ref "R12") (pin "1") (pinfunction "1_1") (pintype "passive"))
      (node (ref "U3") (pin "8") (pinfunction "SEL_8") (pintype "passive"))
    )
    (net (code "71") (name "Net-(U3-V1N)") (class "Default")
      (node (ref "C13") (pin "2") (pinfunction "2_2") (pintype "passive"))
      (node (ref "R11") (pin "1") (pinfunction "1_1") (pintype "passive"))
      (node (ref "U3") (pin "3") (pinfunction "V1N_3") (pintype "passive"))
    )
    (net (code "72") (name "Net-(U3-V1P)") (class "Default")
      (node (ref "C9") (pin "1") (pinfunction "1_1") (pintype "passive"))
      (node (ref "R7") (pin "1") (pinfunction "1_1") (pintype "passive"))
      (node (ref "U3") (pin "2") (pinfunction "V1P_2") (pintype "passive"))
    )
    (net (code "73") (name "Net-(U3-V2P)") (class "Default")
      (node (ref "C14") (pin "1") (pinfunction "1_1") (pintype "passive"))
      (node (ref "R16") (pin "1") (pinfunction "1_1") (pintype "passive"))
      (node (ref "R17") (pin "1") (pinfunction "1_1") (pintype "passive"))
      (node (ref "U3") (pin "4") (pinfunction "V2P_4") (pintype "passive"))
    )
    (net (code "74") (name "Net-(U4-A1)") (class "Default")
      (node (ref "R8") (pin "1") (pinfunction "1_1") (pintype "passive"))
      (node (ref "U4") (pin "1") (pinfunction "A1_1") (pintype "passive"))
    )
    (net (code "75") (name "Net-(U5-FB)") (class "Default")
      (node (ref "C17") (pin "1") (pinfunction "1_1") (pintype "passive"))
      (node (ref "R18") (pin "2") (pinfunction "2_2") (pintype "passive"))
      (node (ref "R20") (pin "2") (pinfunction "2_2") (pintype "passive"))
      (node (ref "U5") (pin "5") (pinfunction "FB_5") (pintype "passive"))
    )
    (net (code "76") (name "Net-(U5-SW)") (class "Default")
      (node (ref "L2") (pin "1") (pinfunction "1_1") (pintype "passive"))
      (node (ref "U5") (pin "3") (pinfunction "SW_3") (pintype "passive"))
    )
    (net (code "77") (name "unconnected-(KEY1-Pad3)") (class "Default")
      (node (ref "KEY1") (pin "3") (pinfunction "3_3") (pintype "passive+no_connect"))
    )
    (net (code "78") (name "unconnected-(KEY1-Pad4)") (class "Default")
      (node (ref "KEY1") (pin "4") (pinfunction "4_4") (pintype "passive+no_connect"))
    )
    (net (code "79") (name "unconnected-(KEY2-Pad3)") (class "Default")
      (node (ref "KEY2") (pin "3") (pinfunction "3_3") (pintype "passive+no_connect"))
    )
    (net (code "80") (name "unconnected-(KEY2-Pad4)") (class "Default")
      (node (ref "KEY2") (pin "4") (pinfunction "4_4") (pintype "passive+no_connect"))
    )
    (net (code "81") (name "unconnected-(P1-D2-Pad20)") (class "Default")
      (node (ref "P1") (pin "20") (pinfunction "D2_20") (pintype "passive+no_connect"))
    )
    (net (code "82") (name "unconnected-(P1-NC-Pad7)") (class "Default")
      (node (ref "P1") (pin "7") (pinfunction "NC_7") (pintype "passive+no_connect"))
    )
    (net (code "83") (name "unconnected-(P5-Pad4)") (class "Default")
      (node (ref "P5") (pin "4") (pintype "passive"))
    )
    (net (code "84") (name "unconnected-(U3-CF1-Pad7)") (class "Default")
      (node (ref "U3") (pin "7") (pinfunction "CF1_7") (pintype "passive+no_connect"))
    )
  )
)
